# PROIECT_TSC.net
KiCad netlist of a schematic drawn in EAGLE
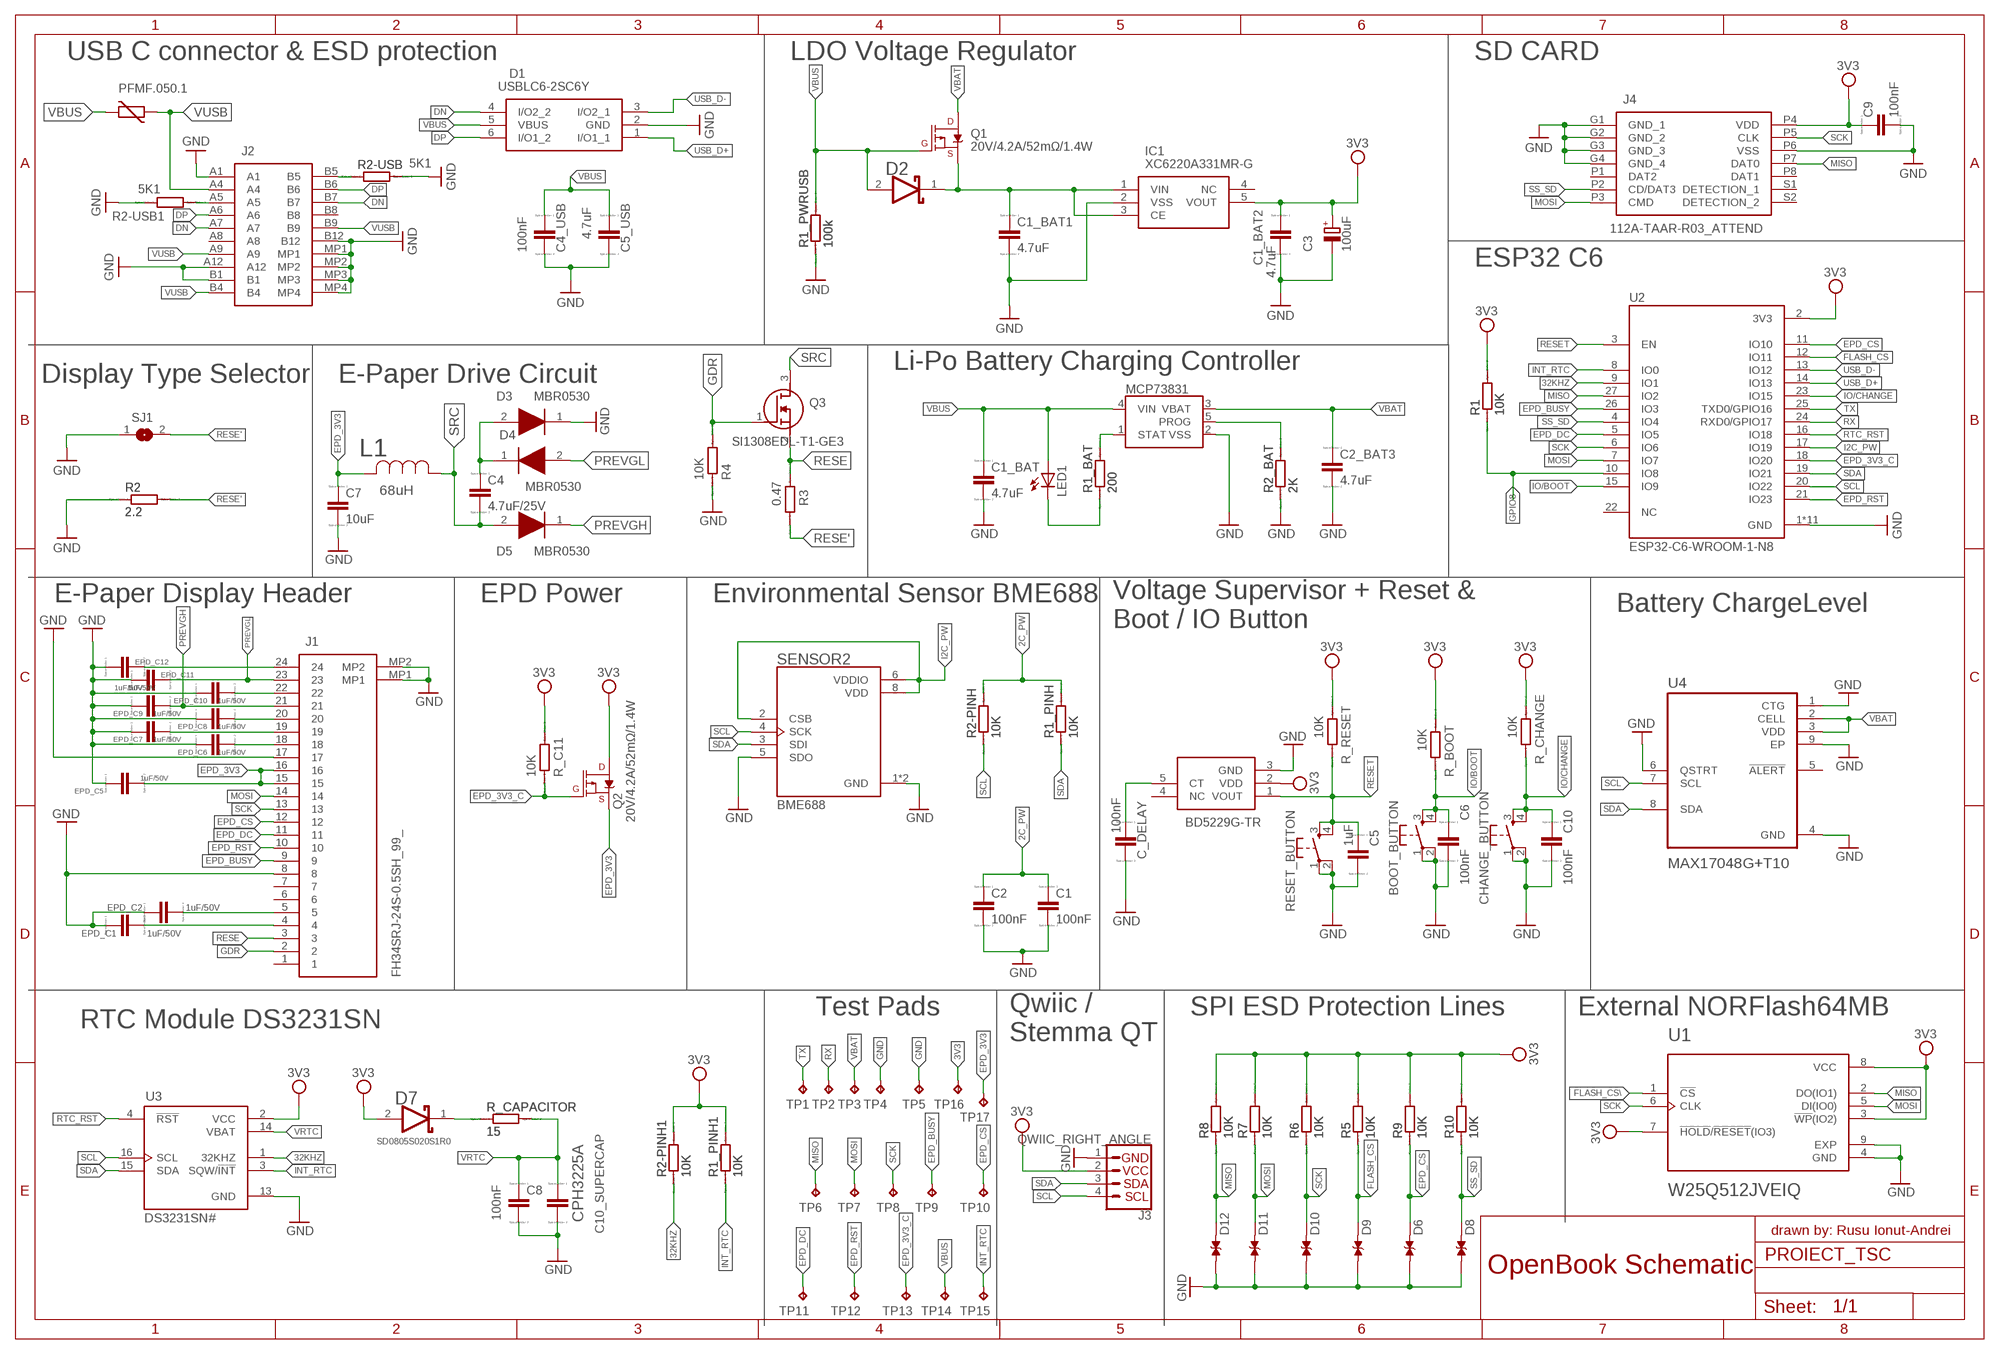
[diagram p0: schematic, sheet 1]

(export (version "E")
  (design (tool "Eeschema 10.0.6"))
  (components
    (comp (ref "BOOT_BUTTON")
      (value "BUTTON_CUSYOMV1")
      (footprint "eagle-import:MYBUTTON")
      (libsource (lib "eagle-import") (part "BUTTON_CUSYOMV1"))
    )
    (comp (ref "C1")
      (value "100nF")
      (footprint "eagle-import:ESP32_WROVER_EAGLE-LTSPICE_C0402")
      (libsource (lib "eagle-import") (part "ESP32_WROVER_EAGLE-LTSPICE_CC0402"))
    )
    (comp (ref "C1_BAT")
      (value "4.7uF")
      (footprint "eagle-import:ESP32_WROVER_EAGLE-LTSPICE_C0402")
      (libsource (lib "eagle-import") (part "ESP32_WROVER_EAGLE-LTSPICE_CC0402"))
    )
    (comp (ref "C1_BAT1")
      (value "4.7uF")
      (footprint "eagle-import:ESP32_WROVER_EAGLE-LTSPICE_C0402")
      (libsource (lib "eagle-import") (part "ESP32_WROVER_EAGLE-LTSPICE_CC0402"))
    )
    (comp (ref "C1_BAT2")
      (value "4.7uF")
      (footprint "eagle-import:EAGLE-LTSPICE_C0402")
      (libsource (lib "eagle-import") (part "EAGLE-LTSPICE_CC0402"))
    )
    (comp (ref "C2")
      (value "100nF")
      (footprint "eagle-import:ESP32_WROVER_EAGLE-LTSPICE_C0402")
      (libsource (lib "eagle-import") (part "ESP32_WROVER_EAGLE-LTSPICE_CC0402"))
    )
    (comp (ref "C2_BAT3")
      (value "4.7uF")
      (footprint "eagle-import:ESP32_WROVER_EAGLE-LTSPICE_C0402")
      (libsource (lib "eagle-import") (part "ESP32_WROVER_EAGLE-LTSPICE_CC0402"))
    )
    (comp (ref "C3")
      (value "100uF")
      (footprint "eagle-import:RCL_CT3528")
      (libsource (lib "eagle-import") (part "RCL_CPOL-EUCT3528"))
    )
    (comp (ref "C4")
      (value "4.7uF/25V")
      (footprint "eagle-import:ESP32_WROVER_EAGLE-LTSPICE_C0402")
      (libsource (lib "eagle-import") (part "ESP32_WROVER_EAGLE-LTSPICE_CC0402"))
    )
    (comp (ref "C4_USB")
      (value "100nF")
      (footprint "eagle-import:EAGLE-LTSPICE_C0402")
      (libsource (lib "eagle-import") (part "EAGLE-LTSPICE_CC0402"))
    )
    (comp (ref "C5")
      (value "1uF")
      (footprint "eagle-import:ESP32_WROVER_EAGLE-LTSPICE_C0402")
      (libsource (lib "eagle-import") (part "ESP32_WROVER_EAGLE-LTSPICE_CC0402"))
    )
    (comp (ref "C5_USB")
      (value "4.7uF")
      (footprint "eagle-import:EAGLE-LTSPICE_C0402")
      (libsource (lib "eagle-import") (part "EAGLE-LTSPICE_CC0402"))
    )
    (comp (ref "C6")
      (value "100nF")
      (footprint "eagle-import:ESP32_WROVER_EAGLE-LTSPICE_C0402")
      (libsource (lib "eagle-import") (part "ESP32_WROVER_EAGLE-LTSPICE_CC0402"))
    )
    (comp (ref "C7")
      (value "10uF")
      (footprint "eagle-import:EAGLE-LTSPICE_C0402")
      (libsource (lib "eagle-import") (part "EAGLE-LTSPICE_CC0402"))
    )
    (comp (ref "C8")
      (value "100nF")
      (footprint "eagle-import:ESP32_WROVER_EAGLE-LTSPICE_C0402")
      (libsource (lib "eagle-import") (part "ESP32_WROVER_EAGLE-LTSPICE_CC0402"))
    )
    (comp (ref "C9")
      (value "100nF")
      (footprint "eagle-import:ESP32_WROVER_EAGLE-LTSPICE_C0402")
      (libsource (lib "eagle-import") (part "ESP32_WROVER_EAGLE-LTSPICE_CC0402"))
    )
    (comp (ref "C10")
      (value "100nF")
      (footprint "eagle-import:ESP32_WROVER_EAGLE-LTSPICE_C0402")
      (libsource (lib "eagle-import") (part "ESP32_WROVER_EAGLE-LTSPICE_CC0402"))
    )
    (comp (ref "C10_SUPERCAP")
      (value "ESP32_WROVER_EAGLE-LTSPICE_CC0402")
      (footprint "eagle-import:ESP32_WROVER_EAGLE-LTSPICE_C0402")
      (libsource (lib "eagle-import") (part "ESP32_WROVER_EAGLE-LTSPICE_CC0402"))
    )
    (comp (ref "CHANGE_BUTTON")
      (value "BUTTON_CUSYOMV1")
      (footprint "eagle-import:MYBUTTON")
      (libsource (lib "eagle-import") (part "BUTTON_CUSYOMV1"))
    )
    (comp (ref "C_DELAY")
      (value "100nF")
      (footprint "eagle-import:ESP32_WROVER_EAGLE-LTSPICE_C0402")
      (libsource (lib "eagle-import") (part "ESP32_WROVER_EAGLE-LTSPICE_CC0402"))
    )
    (comp (ref "D1")
      (value "USBLC6-2SC6Y")
      (footprint "eagle-import:SOT95P280X145-6N")
      (fields (field (name "MF") "STMicroelectronics"))
      (libsource (lib "eagle-import") (part "USBLC6-2SC6Y"))
    )
    (comp (ref "D2")
      (value "ESP32_WROVER_AVX---SD0805S020S1R0_AVX_SD0805S020S1R0_0_0AVX_SD0805S020S1R0_0_0")
      (footprint "eagle-import:ESP32_WROVER_AVX---SD0805S020S1R0_AVX_SD0805S020S1R0_0")
      (fields
        (field (name "DIGIKEY_PART_NUMBER") "478-7800-1-ND")
        (field (name "MF") "AVX")
        (field (name "MOUSER_PART_NUMBER") "581-SD0805S020S1R0")
      )
      (libsource (lib "eagle-import") (part "ESP32_WROVER_AVX---SD0805S020S1R0_AVX_SD0805S020S1R0_0_0AVX_SD0805S020S1R0_0_0"))
    )
    (comp (ref "D3")
      (value "MBR0530")
      (footprint "eagle-import:SOD3716X135N")
      (fields (field (name "MF") "ON Semiconductor"))
      (libsource (lib "eagle-import") (part "MBR0530"))
    )
    (comp (ref "D4")
      (value "MBR0530")
      (footprint "eagle-import:SOD3716X135N")
      (fields (field (name "MF") "ON Semiconductor"))
      (libsource (lib "eagle-import") (part "MBR0530"))
    )
    (comp (ref "D5")
      (value "MBR0530")
      (footprint "eagle-import:SOD3716X135N")
      (fields (field (name "MF") "ON Semiconductor"))
      (libsource (lib "eagle-import") (part "MBR0530"))
    )
    (comp (ref "D6")
      (value "PGB1010603MR")
      (footprint "eagle-import:DIOC1608X36N")
      (fields (field (name "MF") "Littelfuse Inc."))
      (libsource (lib "eagle-import") (part "PGB1010603MR"))
    )
    (comp (ref "D7")
      (value "ESP32_WROVER_AVX---SD0805S020S1R0_AVX_SD0805S020S1R0_0_0AVX_SD0805S020S1R0_0_0")
      (footprint "eagle-import:ESP32_WROVER_AVX---SD0805S020S1R0_AVX_SD0805S020S1R0_0")
      (fields
        (field (name "DIGIKEY_PART_NUMBER") "478-7800-1-ND")
        (field (name "MF") "AVX")
        (field (name "MOUSER_PART_NUMBER") "581-SD0805S020S1R0")
      )
      (libsource (lib "eagle-import") (part "ESP32_WROVER_AVX---SD0805S020S1R0_AVX_SD0805S020S1R0_0_0AVX_SD0805S020S1R0_0_0"))
    )
    (comp (ref "D8")
      (value "PGB1010603MR")
      (footprint "eagle-import:DIOC1608X36N")
      (fields (field (name "MF") "Littelfuse Inc."))
      (libsource (lib "eagle-import") (part "PGB1010603MR"))
    )
    (comp (ref "D9")
      (value "PGB1010603MR")
      (footprint "eagle-import:DIOC1608X36N")
      (fields (field (name "MF") "Littelfuse Inc."))
      (libsource (lib "eagle-import") (part "PGB1010603MR"))
    )
    (comp (ref "D10")
      (value "PGB1010603MR")
      (footprint "eagle-import:DIOC1608X36N")
      (fields (field (name "MF") "Littelfuse Inc."))
      (libsource (lib "eagle-import") (part "PGB1010603MR"))
    )
    (comp (ref "D11")
      (value "PGB1010603MR")
      (footprint "eagle-import:DIOC1608X36N")
      (fields (field (name "MF") "Littelfuse Inc."))
      (libsource (lib "eagle-import") (part "PGB1010603MR"))
    )
    (comp (ref "D12")
      (value "PGB1010603MR")
      (footprint "eagle-import:DIOC1608X36N")
      (fields (field (name "MF") "Littelfuse Inc."))
      (libsource (lib "eagle-import") (part "PGB1010603MR"))
    )
    (comp (ref "EPD_C1")
      (value "1uF/50V")
      (footprint "eagle-import:ESP32_WROVER_EAGLE-LTSPICE_C0402")
      (libsource (lib "eagle-import") (part "ESP32_WROVER_EAGLE-LTSPICE_CC0402"))
    )
    (comp (ref "EPD_C2")
      (value "1uF/50V")
      (footprint "eagle-import:ESP32_WROVER_EAGLE-LTSPICE_C0402")
      (libsource (lib "eagle-import") (part "ESP32_WROVER_EAGLE-LTSPICE_CC0402"))
    )
    (comp (ref "EPD_C5")
      (value "1uF/50V")
      (footprint "eagle-import:ESP32_WROVER_EAGLE-LTSPICE_C0402")
      (libsource (lib "eagle-import") (part "ESP32_WROVER_EAGLE-LTSPICE_CC0402"))
    )
    (comp (ref "EPD_C6")
      (value "1uF/50V")
      (footprint "eagle-import:ESP32_WROVER_EAGLE-LTSPICE_C0402")
      (libsource (lib "eagle-import") (part "ESP32_WROVER_EAGLE-LTSPICE_CC0402"))
    )
    (comp (ref "EPD_C7")
      (value "1uF/50V")
      (footprint "eagle-import:ESP32_WROVER_EAGLE-LTSPICE_C0402")
      (libsource (lib "eagle-import") (part "ESP32_WROVER_EAGLE-LTSPICE_CC0402"))
    )
    (comp (ref "EPD_C8")
      (value "1uF/50V")
      (footprint "eagle-import:ESP32_WROVER_EAGLE-LTSPICE_C0402")
      (libsource (lib "eagle-import") (part "ESP32_WROVER_EAGLE-LTSPICE_CC0402"))
    )
    (comp (ref "EPD_C9")
      (value "1uF/50V")
      (footprint "eagle-import:ESP32_WROVER_EAGLE-LTSPICE_C0402")
      (libsource (lib "eagle-import") (part "ESP32_WROVER_EAGLE-LTSPICE_CC0402"))
    )
    (comp (ref "EPD_C10")
      (value "1uF/50V")
      (footprint "eagle-import:ESP32_WROVER_EAGLE-LTSPICE_C0402")
      (libsource (lib "eagle-import") (part "ESP32_WROVER_EAGLE-LTSPICE_CC0402"))
    )
    (comp (ref "EPD_C11")
      (value "1uF/50V")
      (footprint "eagle-import:ESP32_WROVER_EAGLE-LTSPICE_C0402")
      (libsource (lib "eagle-import") (part "ESP32_WROVER_EAGLE-LTSPICE_CC0402"))
    )
    (comp (ref "EPD_C12")
      (value "1uF/50V")
      (footprint "eagle-import:ESP32_WROVER_EAGLE-LTSPICE_C0402")
      (libsource (lib "eagle-import") (part "ESP32_WROVER_EAGLE-LTSPICE_CC0402"))
    )
    (comp (ref "IC1")
      (value "XC6220A331MR-G")
      (footprint "eagle-import:SOT95P280X120-5N")
      (fields (field (name "MOUSER_PART_NUMBER") "865-XC6220A331MR-G"))
      (libsource (lib "eagle-import") (part "XC6220A331MR-G"))
    )
    (comp (ref "IC2")
      (value "BD5229G-TR")
      (footprint "eagle-import:SOT95P280X125-5N")
      (fields (field (name "MOUSER_PART_NUMBER") "755-BD5229G-TR"))
      (libsource (lib "eagle-import") (part "BD5229G-TR"))
    )
    (comp (ref "J1")
      (value "FH34SRJ-24S-0.5SH_99_")
      (footprint "eagle-import:FH34SRJ24S05SH99")
      (fields
        (field (name "MANUFACTURER_PART_NUMBER") "FH34SRJ-24S-0.5SH(99)")
        (field (name "MOUSER_PART_NUMBER") "798-FH34SRJ24S05SH99")
      )
      (libsource (lib "eagle-import") (part "FH34SRJ-24S-0.5SH_99_"))
    )
    (comp (ref "J2")
      (value "SAMACSYS_PARTS_USB4110-GF-A")
      (footprint "eagle-import:SAMACSYS_PARTS_USB4110GFA")
      (fields
        (field (name "MANUFACTURER_PART_NUMBER") "USB4110-GF-A")
        (field (name "MOUSER_PART_NUMBER") "640-USB4110-GF-A")
      )
      (libsource (lib "eagle-import") (part "SAMACSYS_PARTS_USB4110-GF-A"))
    )
    (comp (ref "J3")
      (value "QWIIC_RIGHT_ANGLE")
      (footprint "eagle-import:JST04_1MM_RA")
      (libsource (lib "eagle-import") (part "QWIIC_CONNECTORJS-1MM"))
    )
    (comp (ref "J4")
      (value "112A-TAAR-R03_ATTEND")
      (footprint "eagle-import:112ATAARR03ATTEND")
      (fields (field (name "MANUFACTURER_PART_NUMBER") "112A-TAAR-R03 ATTEND"))
      (libsource (lib "eagle-import") (part "112A-TAAR-R03_ATTEND"))
    )
    (comp (ref "L1")
      (value "68uH")
      (footprint "eagle-import:IND_4828-WE-TPC_WRE")
      (fields
        (field (name "MANUFACTURER_PART_NUMBER") "744043680")
        (field (name "COPYRIGHT") "Copyright (C) 2024 Ultra Librarian. All rights reserved.")
      )
      (libsource (lib "eagle-import") (part "744043680IND_4828-WE-TPC_WRE"))
    )
    (comp (ref "LED1")
      (value "ADAFRUIT_LEDCHIP-LED0603")
      (footprint "eagle-import:ADAFRUIT_CHIP-LED0603")
      (libsource (lib "eagle-import") (part "ADAFRUIT_LEDCHIP-LED0603"))
    )
    (comp (ref "MCP73831")
      (value "ESP32_WROVER_SPARKFUN-IC-POWER_MCP73831")
      (footprint "eagle-import:ESP32_WROVER_SPARKFUN-IC-POWER_SOT23-5")
      (libsource (lib "eagle-import") (part "ESP32_WROVER_SPARKFUN-IC-POWER_MCP73831"))
    )
    (comp (ref "PFMF.050.1")
      (value "ESP32C6_VARISTORCN1812")
      (footprint "eagle-import:ESP32C6_VARISTOR_CT_CN1812")
      (libsource (lib "eagle-import") (part "ESP32C6_VARISTORCN1812"))
    )
    (comp (ref "Q1")
      (value "20V/4.2A/52mΩ/1.4W")
      (footprint "eagle-import:ESP32_WROVER_SPARKFUN-DISCRETESEMI_SOT23-3")
      (libsource (lib "eagle-import") (part "ESP32_WROVER_SPARKFUN-DISCRETESEMI_MOSFET_PCH-DMG2305UX-7"))
    )
    (comp (ref "Q2")
      (value "20V/4.2A/52mΩ/1.4W")
      (footprint "eagle-import:ESP32_WROVER_SPARKFUN-DISCRETESEMI_SOT23-3")
      (libsource (lib "eagle-import") (part "ESP32_WROVER_SPARKFUN-DISCRETESEMI_MOSFET_PCH-DMG2305UX-7"))
    )
    (comp (ref "Q3")
      (value "SI1308EDL-T1-GE3")
      (footprint "eagle-import:SOT65P210X110-3N")
      (fields (field (name "MF") "Vishay Siliconix"))
      (libsource (lib "eagle-import") (part "SI1308EDL-T1-GE3"))
    )
    (comp (ref "R1")
      (value "10K")
      (footprint "eagle-import:ESP32_WROVER_EAGLE-LTSPICE_R0402")
      (libsource (lib "eagle-import") (part "ESP32_WROVER_EAGLE-LTSPICE_RR0402"))
    )
    (comp (ref "R1_BAT")
      (value "200")
      (footprint "eagle-import:ESP32_WROVER_EAGLE-LTSPICE_R0402")
      (libsource (lib "eagle-import") (part "ESP32_WROVER_EAGLE-LTSPICE_RR0402"))
    )
    (comp (ref "R1_PINH")
      (value "10K")
      (footprint "eagle-import:ESP32_WROVER_EAGLE-LTSPICE_R0402")
      (libsource (lib "eagle-import") (part "ESP32_WROVER_EAGLE-LTSPICE_RR0402"))
    )
    (comp (ref "R1_PINH1")
      (value "10K")
      (footprint "eagle-import:ESP32_WROVER_EAGLE-LTSPICE_R0402")
      (libsource (lib "eagle-import") (part "ESP32_WROVER_EAGLE-LTSPICE_RR0402"))
    )
    (comp (ref "R1_PWRUSB")
      (value "100k")
      (footprint "eagle-import:ESP32_WROVER_EAGLE-LTSPICE_R0402")
      (libsource (lib "eagle-import") (part "ESP32_WROVER_EAGLE-LTSPICE_RR0402"))
    )
    (comp (ref "R2")
      (value "2.2")
      (footprint "eagle-import:ESP32_WROVER_EAGLE-LTSPICE_R0402")
      (libsource (lib "eagle-import") (part "ESP32_WROVER_EAGLE-LTSPICE_RR0402"))
    )
    (comp (ref "R2-PINH")
      (value "10K")
      (footprint "eagle-import:ESP32_WROVER_EAGLE-LTSPICE_R0402")
      (libsource (lib "eagle-import") (part "ESP32_WROVER_EAGLE-LTSPICE_RR0402"))
    )
    (comp (ref "R2-PINH1")
      (value "10K")
      (footprint "eagle-import:ESP32_WROVER_EAGLE-LTSPICE_R0402")
      (libsource (lib "eagle-import") (part "ESP32_WROVER_EAGLE-LTSPICE_RR0402"))
    )
    (comp (ref "R2-USB")
      (value "5K1")
      (footprint "eagle-import:ESP32_WROVER_EAGLE-LTSPICE_R0402")
      (libsource (lib "eagle-import") (part "ESP32_WROVER_EAGLE-LTSPICE_RR0402"))
    )
    (comp (ref "R2-USB1")
      (value "5K1")
      (footprint "eagle-import:ESP32_WROVER_EAGLE-LTSPICE_R0402")
      (libsource (lib "eagle-import") (part "ESP32_WROVER_EAGLE-LTSPICE_RR0402"))
    )
    (comp (ref "R2_BAT")
      (value "2K")
      (footprint "eagle-import:ESP32_WROVER_EAGLE-LTSPICE_R0402")
      (libsource (lib "eagle-import") (part "ESP32_WROVER_EAGLE-LTSPICE_RR0402"))
    )
    (comp (ref "R3")
      (value "0.47")
      (footprint "eagle-import:ESP32_WROVER_EAGLE-LTSPICE_R0402")
      (libsource (lib "eagle-import") (part "ESP32_WROVER_EAGLE-LTSPICE_RR0402"))
    )
    (comp (ref "R4")
      (value "10K")
      (footprint "eagle-import:ESP32_WROVER_EAGLE-LTSPICE_R0402")
      (libsource (lib "eagle-import") (part "ESP32_WROVER_EAGLE-LTSPICE_RR0402"))
    )
    (comp (ref "R5")
      (value "10K")
      (footprint "eagle-import:ESP32_WROVER_EAGLE-LTSPICE_R0402")
      (libsource (lib "eagle-import") (part "ESP32_WROVER_EAGLE-LTSPICE_RR0402"))
    )
    (comp (ref "R6")
      (value "10K")
      (footprint "eagle-import:ESP32_WROVER_EAGLE-LTSPICE_R0402")
      (libsource (lib "eagle-import") (part "ESP32_WROVER_EAGLE-LTSPICE_RR0402"))
    )
    (comp (ref "R7")
      (value "10K")
      (footprint "eagle-import:ESP32_WROVER_EAGLE-LTSPICE_R0402")
      (libsource (lib "eagle-import") (part "ESP32_WROVER_EAGLE-LTSPICE_RR0402"))
    )
    (comp (ref "R8")
      (value "10K")
      (footprint "eagle-import:ESP32_WROVER_EAGLE-LTSPICE_R0402")
      (libsource (lib "eagle-import") (part "ESP32_WROVER_EAGLE-LTSPICE_RR0402"))
    )
    (comp (ref "R9")
      (value "10K")
      (footprint "eagle-import:ESP32_WROVER_EAGLE-LTSPICE_R0402")
      (libsource (lib "eagle-import") (part "ESP32_WROVER_EAGLE-LTSPICE_RR0402"))
    )
    (comp (ref "R10")
      (value "10K")
      (footprint "eagle-import:ESP32_WROVER_EAGLE-LTSPICE_R0402")
      (libsource (lib "eagle-import") (part "ESP32_WROVER_EAGLE-LTSPICE_RR0402"))
    )
    (comp (ref "RESET_BUTTON")
      (value "BUTTON_CUSYOMV1")
      (footprint "eagle-import:MYBUTTON")
      (libsource (lib "eagle-import") (part "BUTTON_CUSYOMV1"))
    )
    (comp (ref "R_BOOT")
      (value "10K")
      (footprint "eagle-import:ESP32_WROVER_EAGLE-LTSPICE_R0402")
      (libsource (lib "eagle-import") (part "ESP32_WROVER_EAGLE-LTSPICE_RR0402"))
    )
    (comp (ref "R_C11")
      (value "10K")
      (footprint "eagle-import:ESP32_WROVER_EAGLE-LTSPICE_R0402")
      (libsource (lib "eagle-import") (part "ESP32_WROVER_EAGLE-LTSPICE_RR0402"))
    )
    (comp (ref "R_CAPACITOR")
      (value "15")
      (footprint "eagle-import:ESP32_WROVER_EAGLE-LTSPICE_R0402")
      (libsource (lib "eagle-import") (part "ESP32_WROVER_EAGLE-LTSPICE_RR0402"))
    )
    (comp (ref "R_CHANGE")
      (value "10K")
      (footprint "eagle-import:ESP32_WROVER_EAGLE-LTSPICE_R0402")
      (libsource (lib "eagle-import") (part "ESP32_WROVER_EAGLE-LTSPICE_RR0402"))
    )
    (comp (ref "R_RESET")
      (value "10K")
      (footprint "eagle-import:ESP32_WROVER_EAGLE-LTSPICE_R0402")
      (libsource (lib "eagle-import") (part "ESP32_WROVER_EAGLE-LTSPICE_RR0402"))
    )
    (comp (ref "SENSOR2")
      (value "ESP32_WROVER_BME680_BME680")
      (footprint "eagle-import:ESP32_WROVER_BME680_PSON80P300X300X100-8N")
      (fields (field (name "MF") "Bosch Sensortec") (field (name "MP") "BME680"))
      (libsource (lib "eagle-import") (part "ESP32_WROVER_BME680_BME680"))
    )
    (comp (ref "SJ1") (value "SJ") (footprint "eagle-import:SJ") (libsource (lib "eagle-import") (part "SJ")))
    (comp (ref "TP1")
      (value "TPTP20R")
      (footprint "eagle-import:TP20R")
      (libsource (lib "eagle-import") (part "TPTP20R"))
    )
    (comp (ref "TP2")
      (value "TPTP20R")
      (footprint "eagle-import:TP20R")
      (libsource (lib "eagle-import") (part "TPTP20R"))
    )
    (comp (ref "TP3")
      (value "TPTP20R")
      (footprint "eagle-import:TP20R")
      (libsource (lib "eagle-import") (part "TPTP20R"))
    )
    (comp (ref "TP4")
      (value "TPTP20R")
      (footprint "eagle-import:TP20R")
      (libsource (lib "eagle-import") (part "TPTP20R"))
    )
    (comp (ref "TP5")
      (value "TPTP20R")
      (footprint "eagle-import:TP20R")
      (libsource (lib "eagle-import") (part "TPTP20R"))
    )
    (comp (ref "TP6")
      (value "TPTP20R")
      (footprint "eagle-import:TP20R")
      (libsource (lib "eagle-import") (part "TPTP20R"))
    )
    (comp (ref "TP7")
      (value "TPTP20R")
      (footprint "eagle-import:TP20R")
      (libsource (lib "eagle-import") (part "TPTP20R"))
    )
    (comp (ref "TP8")
      (value "TPTP20R")
      (footprint "eagle-import:TP20R")
      (libsource (lib "eagle-import") (part "TPTP20R"))
    )
    (comp (ref "TP9")
      (value "TPTP20R")
      (footprint "eagle-import:TP20R")
      (libsource (lib "eagle-import") (part "TPTP20R"))
    )
    (comp (ref "TP10")
      (value "TPTP20R")
      (footprint "eagle-import:TP20R")
      (libsource (lib "eagle-import") (part "TPTP20R"))
    )
    (comp (ref "TP11")
      (value "TPTP20R")
      (footprint "eagle-import:TP20R")
      (libsource (lib "eagle-import") (part "TPTP20R"))
    )
    (comp (ref "TP12")
      (value "TPTP20R")
      (footprint "eagle-import:TP20R")
      (libsource (lib "eagle-import") (part "TPTP20R"))
    )
    (comp (ref "TP13")
      (value "TPTP20R")
      (footprint "eagle-import:TP20R")
      (libsource (lib "eagle-import") (part "TPTP20R"))
    )
    (comp (ref "TP14")
      (value "TPTP20R")
      (footprint "eagle-import:TP20R")
      (libsource (lib "eagle-import") (part "TPTP20R"))
    )
    (comp (ref "TP15")
      (value "TPTP20R")
      (footprint "eagle-import:TP20R")
      (libsource (lib "eagle-import") (part "TPTP20R"))
    )
    (comp (ref "TP16")
      (value "TPTP20R")
      (footprint "eagle-import:TP20R")
      (libsource (lib "eagle-import") (part "TPTP20R"))
    )
    (comp (ref "TP17")
      (value "TPTP20R")
      (footprint "eagle-import:TP20R")
      (libsource (lib "eagle-import") (part "TPTP20R"))
    )
    (comp (ref "U1")
      (value "W25Q512JVEIQ")
      (footprint "eagle-import:SON127P600X800X80-9N")
      (fields (field (name "MF") "Winbond Electronics"))
      (libsource (lib "eagle-import") (part "W25Q512JVEIQ"))
    )
    (comp (ref "U2")
      (value "ESP32-C6-WROOM-1-N8")
      (footprint "eagle-import:XCVR_ESP32-C6-WROOM-1-N8")
      (fields (field (name "MF") "Espressif Systems"))
      (libsource (lib "eagle-import") (part "ESP32-C6-WROOM-1-N8"))
    )
    (comp (ref "U3")
      (value "DS3231SN#")
      (footprint "eagle-import:SOIC127P1032X265-16N")
      (fields (field (name "MF") "Analog Devices"))
      (libsource (lib "eagle-import") (part "DS3231SN#"))
    )
    (comp (ref "U4")
      (value "MAX17048G+T10")
      (footprint "eagle-import:SON50P200X200X80-9N")
      (fields (field (name "MF") "Analog Devices"))
      (libsource (lib "eagle-import") (part "MAX17048G+T10"))
    )
  )
  (nets
    (net (code "1") (name "2C_PW") (class "Default")
      (node (ref "C1") (pin "1") (pinfunction "1_1") (pintype "passive"))
      (node (ref "C2") (pin "1") (pinfunction "1_1") (pintype "passive"))
      (node (ref "R1_PINH") (pin "2") (pinfunction "2_2") (pintype "passive"))
      (node (ref "R2-PINH") (pin "2") (pinfunction "2_2") (pintype "passive"))
    )
    (net (code "2") (name "3V3") (class "Default")
      (node (ref "C1_BAT2") (pin "1") (pinfunction "1_1") (pintype "passive"))
      (node (ref "C3") (pin "+") (pinfunction "+_+") (pintype "passive"))
      (node (ref "C9") (pin "1") (pinfunction "1_1") (pintype "passive"))
      (node (ref "D7") (pin "2") (pinfunction "ANODE_2") (pintype "bidirectional"))
      (node (ref "IC1") (pin "5") (pinfunction "VOUT_5") (pintype "bidirectional"))
      (node (ref "IC2") (pin "2") (pinfunction "VDD_2") (pintype "bidirectional"))
      (node (ref "J3") (pin "2") (pinfunction "2_2") (pintype "power_in"))
      (node (ref "J4") (pin "P4") (pinfunction "VDD_P4") (pintype "bidirectional"))
      (node (ref "Q2") (pin "3") (pinfunction "D_3") (pintype "bidirectional"))
      (node (ref "R1") (pin "2") (pinfunction "2_2") (pintype "passive"))
      (node (ref "R10") (pin "2") (pinfunction "2_2") (pintype "passive"))
      (node (ref "R1_PINH1") (pin "2") (pinfunction "2_2") (pintype "passive"))
      (node (ref "R2-PINH1") (pin "2") (pinfunction "2_2") (pintype "passive"))
      (node (ref "R5") (pin "2") (pinfunction "2_2") (pintype "passive"))
      (node (ref "R6") (pin "2") (pinfunction "2_2") (pintype "passive"))
      (node (ref "R7") (pin "2") (pinfunction "2_2") (pintype "passive"))
      (node (ref "R8") (pin "2") (pinfunction "2_2") (pintype "passive"))
      (node (ref "R9") (pin "2") (pinfunction "2_2") (pintype "passive"))
      (node (ref "R_BOOT") (pin "2") (pinfunction "2_2") (pintype "passive"))
      (node (ref "R_C11") (pin "2") (pinfunction "2_2") (pintype "passive"))
      (node (ref "R_CHANGE") (pin "2") (pinfunction "2_2") (pintype "passive"))
      (node (ref "R_RESET") (pin "2") (pinfunction "2_2") (pintype "passive"))
      (node (ref "TP16") (pin "TP") (pinfunction "TP_TP") (pintype "input"))
      (node (ref "U1") (pin "3") (pinfunction "~{WP}(IO2)_3") (pintype "bidirectional"))
      (node (ref "U1") (pin "7") (pinfunction "~{HOLD}/~{RESET}(IO3)_7") (pintype "bidirectional"))
      (node (ref "U1") (pin "8") (pinfunction "VCC_8") (pintype "power_in"))
      (node (ref "U2") (pin "2") (pinfunction "3V3_2") (pintype "power_in"))
      (node (ref "U3") (pin "2") (pinfunction "VCC_2") (pintype "power_in"))
    )
    (net (code "3") (name "32KHZ") (class "Default")
      (node (ref "R2-PINH1") (pin "1") (pinfunction "1_1") (pintype "passive"))
      (node (ref "U2") (pin "9") (pinfunction "IO1_9") (pintype "bidirectional"))
      (node (ref "U3") (pin "1") (pinfunction "32KHZ_1") (pintype "output"))
    )
    (net (code "4") (name "DN") (class "Default")
      (node (ref "D1") (pin "4") (pinfunction "I/O2_2_4") (pintype "bidirectional"))
      (node (ref "J2") (pin "A7") (pinfunction "A7_A7") (pintype "bidirectional"))
      (node (ref "J2") (pin "B7") (pinfunction "B7_B7") (pintype "bidirectional"))
    )
    (net (code "5") (name "DP") (class "Default")
      (node (ref "D1") (pin "6") (pinfunction "I/O1_2_6") (pintype "bidirectional"))
      (node (ref "J2") (pin "A6") (pinfunction "A6_A6") (pintype "bidirectional"))
      (node (ref "J2") (pin "B6") (pinfunction "B6_B6") (pintype "bidirectional"))
    )
    (net (code "6") (name "EPD_3V3") (class "Default")
      (node (ref "C7") (pin "1") (pinfunction "1_1") (pintype "passive"))
      (node (ref "EPD_C5") (pin "2") (pinfunction "2_2") (pintype "passive"))
      (node (ref "J1") (pin "15") (pinfunction "15_15") (pintype "bidirectional"))
      (node (ref "J1") (pin "16") (pinfunction "16_16") (pintype "bidirectional"))
      (node (ref "L1") (pin "2") (pinfunction "2_2") (pintype "passive"))
      (node (ref "Q2") (pin "2") (pinfunction "S_2") (pintype "bidirectional"))
      (node (ref "TP17") (pin "TP") (pinfunction "TP_TP") (pintype "input"))
    )
    (net (code "7") (name "EPD_3V3_C") (class "Default")
      (node (ref "Q2") (pin "1") (pinfunction "G_1") (pintype "bidirectional"))
      (node (ref "R_C11") (pin "1") (pinfunction "1_1") (pintype "passive"))
      (node (ref "TP13") (pin "TP") (pinfunction "TP_TP") (pintype "input"))
      (node (ref "U2") (pin "18") (pinfunction "IO20_18") (pintype "bidirectional"))
    )
    (net (code "8") (name "EPD_BUSY") (class "Default")
      (node (ref "J1") (pin "9") (pinfunction "9_9") (pintype "bidirectional"))
      (node (ref "TP9") (pin "TP") (pinfunction "TP_TP") (pintype "input"))
      (node (ref "U2") (pin "26") (pinfunction "IO3_26") (pintype "bidirectional"))
    )
    (net (code "9") (name "EPD_CS") (class "Default")
      (node (ref "D6") (pin "2") (pinfunction "2_2") (pintype "passive"))
      (node (ref "J1") (pin "12") (pinfunction "12_12") (pintype "bidirectional"))
      (node (ref "R9") (pin "1") (pinfunction "1_1") (pintype "passive"))
      (node (ref "TP10") (pin "TP") (pinfunction "TP_TP") (pintype "input"))
      (node (ref "U2") (pin "11") (pinfunction "IO10_11") (pintype "bidirectional"))
    )
    (net (code "10") (name "EPD_DC") (class "Default")
      (node (ref "J1") (pin "11") (pinfunction "11_11") (pintype "bidirectional"))
      (node (ref "TP11") (pin "TP") (pinfunction "TP_TP") (pintype "input"))
      (node (ref "U2") (pin "5") (pinfunction "IO5_5") (pintype "bidirectional"))
    )
    (net (code "11") (name "EPD_RST") (class "Default")
      (node (ref "J1") (pin "10") (pinfunction "10_10") (pintype "bidirectional"))
      (node (ref "TP12") (pin "TP") (pinfunction "TP_TP") (pintype "input"))
      (node (ref "U2") (pin "21") (pinfunction "IO23_21") (pintype "bidirectional"))
    )
    (net (code "12") (name "FLASH_CS") (class "Default")
      (node (ref "D9") (pin "2") (pinfunction "2_2") (pintype "passive"))
      (node (ref "R5") (pin "1") (pinfunction "1_1") (pintype "passive"))
      (node (ref "U2") (pin "12") (pinfunction "IO11_12") (pintype "bidirectional"))
    )
    (net (code "13") (name "FLASH_CS\\") (class "Default")
      (node (ref "U1") (pin "1") (pinfunction "~{CS}_1") (pintype "input"))
    )
    (net (code "14") (name "GDR") (class "Default")
      (node (ref "J1") (pin "2") (pinfunction "2_2") (pintype "bidirectional"))
      (node (ref "Q3") (pin "1") (pinfunction "G_1") (pintype "bidirectional"))
      (node (ref "R4") (pin "2") (pinfunction "2_2") (pintype "passive"))
    )
    (net (code "15") (name "GND") (class "Default")
      (node (ref "BOOT_BUTTON") (pin "1") (pinfunction "1_1") (pintype "passive"))
      (node (ref "BOOT_BUTTON") (pin "2") (pinfunction "2_2") (pintype "passive"))
      (node (ref "C1") (pin "2") (pinfunction "2_2") (pintype "passive"))
      (node (ref "C10") (pin "2") (pinfunction "2_2") (pintype "passive"))
      (node (ref "C10_SUPERCAP") (pin "2") (pinfunction "2_2") (pintype "passive"))
      (node (ref "C1_BAT") (pin "2") (pinfunction "2_2") (pintype "passive"))
      (node (ref "C1_BAT1") (pin "2") (pinfunction "2_2") (pintype "passive"))
      (node (ref "C1_BAT2") (pin "2") (pinfunction "2_2") (pintype "passive"))
      (node (ref "C2") (pin "2") (pinfunction "2_2") (pintype "passive"))
      (node (ref "C2_BAT3") (pin "2") (pinfunction "2_2") (pintype "passive"))
      (node (ref "C3") (pin "-") (pinfunction "-_-") (pintype "passive"))
      (node (ref "C4_USB") (pin "2") (pinfunction "2_2") (pintype "passive"))
      (node (ref "C5") (pin "2") (pinfunction "2_2") (pintype "passive"))
      (node (ref "C5_USB") (pin "2") (pinfunction "2_2") (pintype "passive"))
      (node (ref "C6") (pin "2") (pinfunction "2_2") (pintype "passive"))
      (node (ref "C7") (pin "2") (pinfunction "2_2") (pintype "passive"))
      (node (ref "C8") (pin "2") (pinfunction "2_2") (pintype "passive"))
      (node (ref "C9") (pin "2") (pinfunction "2_2") (pintype "passive"))
      (node (ref "CHANGE_BUTTON") (pin "1") (pinfunction "1_1") (pintype "passive"))
      (node (ref "CHANGE_BUTTON") (pin "2") (pinfunction "2_2") (pintype "passive"))
      (node (ref "C_DELAY") (pin "2") (pinfunction "2_2") (pintype "passive"))
      (node (ref "D1") (pin "2") (pinfunction "GND_2") (pintype "bidirectional"))
      (node (ref "D10") (pin "1") (pinfunction "1_1") (pintype "passive"))
      (node (ref "D11") (pin "1") (pinfunction "1_1") (pintype "passive"))
      (node (ref "D12") (pin "1") (pinfunction "1_1") (pintype "passive"))
      (node (ref "D3") (pin "1") (pinfunction "K_1") (pintype "bidirectional"))
      (node (ref "D6") (pin "1") (pinfunction "1_1") (pintype "passive"))
      (node (ref "D8") (pin "1") (pinfunction "1_1") (pintype "passive"))
      (node (ref "D9") (pin "1") (pinfunction "1_1") (pintype "passive"))
      (node (ref "EPD_C1") (pin "1") (pinfunction "1_1") (pintype "passive"))
      (node (ref "EPD_C10") (pin "1") (pinfunction "1_1") (pintype "passive"))
      (node (ref "EPD_C11") (pin "1") (pinfunction "1_1") (pintype "passive"))
      (node (ref "EPD_C12") (pin "1") (pinfunction "1_1") (pintype "passive"))
      (node (ref "EPD_C2") (pin "1") (pinfunction "1_1") (pintype "passive"))
      (node (ref "EPD_C5") (pin "1") (pinfunction "1_1") (pintype "passive"))
      (node (ref "EPD_C6") (pin "1") (pinfunction "1_1") (pintype "passive"))
      (node (ref "EPD_C7") (pin "1") (pinfunction "1_1") (pintype "passive"))
      (node (ref "EPD_C8") (pin "1") (pinfunction "1_1") (pintype "passive"))
      (node (ref "EPD_C9") (pin "1") (pinfunction "1_1") (pintype "passive"))
      (node (ref "IC1") (pin "2") (pinfunction "VSS_2") (pintype "bidirectional"))
      (node (ref "IC2") (pin "3") (pinfunction "GND_3") (pintype "bidirectional"))
      (node (ref "J1") (pin "17") (pinfunction "17_17") (pintype "bidirectional"))
      (node (ref "J1") (pin "8") (pinfunction "8_8") (pintype "bidirectional"))
      (node (ref "J1") (pin "MP1") (pinfunction "MP1_MP1") (pintype "bidirectional"))
      (node (ref "J1") (pin "MP2") (pinfunction "MP2_MP2") (pintype "bidirectional"))
      (node (ref "J2") (pin "A1") (pinfunction "A1_A1") (pintype "bidirectional"))
      (node (ref "J2") (pin "A12") (pinfunction "A12_A12") (pintype "bidirectional"))
      (node (ref "J2") (pin "B1") (pinfunction "B1_B1") (pintype "bidirectional"))
      (node (ref "J2") (pin "B12") (pinfunction "B12_B12") (pintype "bidirectional"))
      (node (ref "J2") (pin "MP1") (pinfunction "MP1_MP1") (pintype "bidirectional"))
      (node (ref "J2") (pin "MP2") (pinfunction "MP2_MP2") (pintype "bidirectional"))
      (node (ref "J2") (pin "MP3") (pinfunction "MP3_MP3") (pintype "bidirectional"))
      (node (ref "J2") (pin "MP4") (pinfunction "MP4_MP4") (pintype "bidirectional"))
      (node (ref "J3") (pin "1") (pinfunction "1_1") (pintype "power_in"))
      (node (ref "J4") (pin "G1") (pinfunction "GND_1_G1") (pintype "bidirectional"))
      (node (ref "J4") (pin "G2") (pinfunction "GND_2_G2") (pintype "bidirectional"))
      (node (ref "J4") (pin "G3") (pinfunction "GND_3_G3") (pintype "bidirectional"))
      (node (ref "J4") (pin "G4") (pinfunction "GND_4_G4") (pintype "bidirectional"))
      (node (ref "J4") (pin "P6") (pinfunction "VSS_P6") (pintype "bidirectional"))
      (node (ref "MCP73831") (pin "2") (pinfunction "VSS_2") (pintype "power_in"))
      (node (ref "R1_PWRUSB") (pin "1") (pinfunction "1_1") (pintype "passive"))
      (node (ref "R2") (pin "1") (pinfunction "1_1") (pintype "passive"))
      (node (ref "R2-USB") (pin "2") (pinfunction "2_2") (pintype "passive"))
      (node (ref "R2-USB1") (pin "1") (pinfunction "1_1") (pintype "passive"))
      (node (ref "R2_BAT") (pin "1") (pinfunction "1_1") (pintype "passive"))
      (node (ref "R4") (pin "1") (pinfunction "1_1") (pintype "passive"))
      (node (ref "RESET_BUTTON") (pin "1") (pinfunction "1_1") (pintype "passive"))
      (node (ref "RESET_BUTTON") (pin "2") (pinfunction "2_2") (pintype "passive"))
      (node (ref "SENSOR2") (pin "1") (pinfunction "GND_1") (pintype "power_in"))
      (node (ref "SENSOR2") (pin "5") (pinfunction "SDO_5") (pintype "bidirectional"))
      (node (ref "SENSOR2") (pin "7") (pinfunction "GND_7") (pintype "power_in"))
      (node (ref "SJ1") (pin "1") (pinfunction "1_1") (pintype "passive"))
      (node (ref "TP4") (pin "TP") (pinfunction "TP_TP") (pintype "input"))
      (node (ref "TP5") (pin "TP") (pinfunction "TP_TP") (pintype "input"))
      (node (ref "U1") (pin "4") (pinfunction "GND_4") (pintype "power_in"))
      (node (ref "U1") (pin "9") (pinfunction "EXP_9") (pintype "passive"))
      (node (ref "U2") (pin "1") (pinfunction "GND_1") (pintype "power_in"))
      (node (ref "U2") (pin "28") (pinfunction "GND_28") (pintype "power_in"))
      (node (ref "U2") (pin "29_1") (pinfunction "GND_29_1") (pintype "power_in"))
      (node (ref "U2") (pin "29_2") (pinfunction "GND_29_2") (pintype "power_in"))
      (node (ref "U2") (pin "29_3") (pinfunction "GND_29_3") (pintype "power_in"))
      (node (ref "U2") (pin "29_4") (pinfunction "GND_29_4") (pintype "power_in"))
      (node (ref "U2") (pin "29_5") (pinfunction "GND_29_5") (pintype "power_in"))
      (node (ref "U2") (pin "29_6") (pinfunction "GND_29_6") (pintype "power_in"))
      (node (ref "U2") (pin "29_7") (pinfunction "GND_29_7") (pintype "power_in"))
      (node (ref "U2") (pin "29_8") (pinfunction "GND_29_8") (pintype "power_in"))
      (node (ref "U2") (pin "29_9") (pinfunction "GND_29_9") (pintype "power_in"))
      (node (ref "U3") (pin "13") (pinfunction "GND_13") (pintype "power_in"))
      (node (ref "U4") (pin "1") (pinfunction "CTG_1") (pintype "power_in"))
      (node (ref "U4") (pin "4") (pinfunction "GND_4") (pintype "power_in"))
      (node (ref "U4") (pin "6") (pinfunction "QSTRT_6") (pintype "input"))
      (node (ref "U4") (pin "9") (pinfunction "EP_9") (pintype "power_in"))
    )
    (net (code "16") (name "GPIO8") (class "Default")
      (node (ref "R1") (pin "1") (pinfunction "1_1") (pintype "passive"))
      (node (ref "U2") (pin "10") (pinfunction "IO8_10") (pintype "bidirectional"))
    )
    (net (code "17") (name "I2C_PW") (class "Default")
      (node (ref "SENSOR2") (pin "2") (pinfunction "CSB_2") (pintype "input"))
      (node (ref "SENSOR2") (pin "6") (pinfunction "VDDIO_6") (pintype "power_in"))
      (node (ref "SENSOR2") (pin "8") (pinfunction "VDD_8") (pintype "power_in"))
      (node (ref "U2") (pin "17") (pinfunction "IO19_17") (pintype "bidirectional"))
    )
    (net (code "18") (name "INT_RTC") (class "Default")
      (node (ref "R1_PINH1") (pin "1") (pinfunction "1_1") (pintype "passive"))
      (node (ref "TP15") (pin "TP") (pinfunction "TP_TP") (pintype "input"))
      (node (ref "U2") (pin "8") (pinfunction "IO0_8") (pintype "bidirectional"))
      (node (ref "U3") (pin "3") (pinfunction "SQW/~{INT}_3") (pintype "output"))
    )
    (net (code "19") (name "IO{slash}BOOT") (class "Default")
      (node (ref "BOOT_BUTTON") (pin "3") (pinfunction "3_3") (pintype "passive"))
      (node (ref "BOOT_BUTTON") (pin "4") (pinfunction "4_4") (pintype "passive"))
      (node (ref "C6") (pin "1") (pinfunction "1_1") (pintype "passive"))
      (node (ref "R_BOOT") (pin "1") (pinfunction "1_1") (pintype "passive"))
      (node (ref "U2") (pin "15") (pinfunction "IO9_15") (pintype "bidirectional"))
    )
    (net (code "20") (name "IO{slash}CHANGE") (class "Default")
      (node (ref "C10") (pin "1") (pinfunction "1_1") (pintype "passive"))
      (node (ref "CHANGE_BUTTON") (pin "3") (pinfunction "3_3") (pintype "passive"))
      (node (ref "CHANGE_BUTTON") (pin "4") (pinfunction "4_4") (pintype "passive"))
      (node (ref "R_CHANGE") (pin "1") (pinfunction "1_1") (pintype "passive"))
      (node (ref "U2") (pin "23") (pinfunction "IO15_23") (pintype "bidirectional"))
    )
    (net (code "21") (name "MISO") (class "Default")
      (node (ref "D12") (pin "2") (pinfunction "2_2") (pintype "passive"))
      (node (ref "J4") (pin "P7") (pinfunction "DAT0_P7") (pintype "bidirectional"))
      (node (ref "R8") (pin "1") (pinfunction "1_1") (pintype "passive"))
      (node (ref "TP6") (pin "TP") (pinfunction "TP_TP") (pintype "input"))
      (node (ref "U1") (pin "2") (pinfunction "DO(IO1)_2") (pintype "bidirectional"))
      (node (ref "U2") (pin "27") (pinfunction "IO2_27") (pintype "bidirectional"))
    )
    (net (code "22") (name "MOSI") (class "Default")
      (node (ref "D11") (pin "2") (pinfunction "2_2") (pintype "passive"))
      (node (ref "J1") (pin "14") (pinfunction "14_14") (pintype "bidirectional"))
      (node (ref "J4") (pin "P3") (pinfunction "CMD_P3") (pintype "bidirectional"))
      (node (ref "R7") (pin "1") (pinfunction "1_1") (pintype "passive"))
      (node (ref "TP7") (pin "TP") (pinfunction "TP_TP") (pintype "input"))
      (node (ref "U1") (pin "5") (pinfunction "DI(IO0)_5") (pintype "bidirectional"))
      (node (ref "U2") (pin "7") (pinfunction "IO7_7") (pintype "bidirectional"))
    )
    (net (code "23") (name "Net-(D2-CATHODE)") (class "Default")
      (node (ref "C1_BAT1") (pin "1") (pinfunction "1_1") (pintype "passive"))
      (node (ref "D2") (pin "1") (pinfunction "CATHODE_1") (pintype "bidirectional"))
      (node (ref "IC1") (pin "1") (pinfunction "VIN_1") (pintype "bidirectional"))
      (node (ref "IC1") (pin "3") (pinfunction "CE_3") (pintype "bidirectional"))
      (node (ref "Q1") (pin "2") (pinfunction "S_2") (pintype "bidirectional"))
    )
    (net (code "24") (name "Net-(D3-A)") (class "Default")
      (node (ref "C4") (pin "1") (pinfunction "1_1") (pintype "passive"))
      (node (ref "D3") (pin "2") (pinfunction "A_2") (pintype "bidirectional"))
      (node (ref "D4") (pin "1") (pinfunction "K_1") (pintype "bidirectional"))
    )
    (net (code "25") (name "Net-(D7-CATHODE)") (class "Default")
      (node (ref "D7") (pin "1") (pinfunction "CATHODE_1") (pintype "bidirectional"))
      (node (ref "R_CAPACITOR") (pin "1") (pinfunction "1_1") (pintype "passive"))
    )
    (net (code "26") (name "Net-(EPD_C1-Pad2)") (class "Default")
      (node (ref "EPD_C1") (pin "2") (pinfunction "2_2") (pintype "passive"))
      (node (ref "J1") (pin "4") (pinfunction "4_4") (pintype "bidirectional"))
    )
    (net (code "27") (name "Net-(EPD_C2-Pad2)") (class "Default")
      (node (ref "EPD_C2") (pin "2") (pinfunction "2_2") (pintype "passive"))
      (node (ref "J1") (pin "5") (pinfunction "5_5") (pintype "bidirectional"))
    )
    (net (code "28") (name "Net-(EPD_C6-Pad2)") (class "Default")
      (node (ref "EPD_C6") (pin "2") (pinfunction "2_2") (pintype "passive"))
      (node (ref "J1") (pin "18") (pinfunction "18_18") (pintype "bidirectional"))
    )
    (net (code "29") (name "Net-(EPD_C7-Pad2)") (class "Default")
      (node (ref "EPD_C7") (pin "2") (pinfunction "2_2") (pintype "passive"))
      (node (ref "J1") (pin "19") (pinfunction "19_19") (pintype "bidirectional"))
    )
    (net (code "30") (name "Net-(EPD_C8-Pad2)") (class "Default")
      (node (ref "EPD_C8") (pin "2") (pinfunction "2_2") (pintype "passive"))
      (node (ref "J1") (pin "20") (pinfunction "20_20") (pintype "bidirectional"))
    )
    (net (code "31") (name "Net-(EPD_C10-Pad2)") (class "Default")
      (node (ref "EPD_C10") (pin "2") (pinfunction "2_2") (pintype "passive"))
      (node (ref "J1") (pin "22") (pinfunction "22_22") (pintype "bidirectional"))
    )
    (net (code "32") (name "Net-(EPD_C12-Pad2)") (class "Default")
      (node (ref "EPD_C12") (pin "2") (pinfunction "2_2") (pintype "passive"))
      (node (ref "J1") (pin "24") (pinfunction "24_24") (pintype "bidirectional"))
    )
    (net (code "33") (name "Net-(IC2-CT)") (class "Default")
      (node (ref "C_DELAY") (pin "1") (pinfunction "1_1") (pintype "passive"))
      (node (ref "IC2") (pin "5") (pinfunction "CT_5") (pintype "bidirectional"))
    )
    (net (code "34") (name "Net-(J2-PadA5)") (class "Default")
      (node (ref "J2") (pin "A5") (pinfunction "A5_A5") (pintype "bidirectional"))
      (node (ref "R2-USB1") (pin "2") (pinfunction "2_2") (pintype "passive"))
    )
    (net (code "35") (name "Net-(J2-PadB5)") (class "Default")
      (node (ref "J2") (pin "B5") (pinfunction "B5_B5") (pintype "bidirectional"))
      (node (ref "R2-USB") (pin "1") (pinfunction "1_1") (pintype "passive"))
    )
    (net (code "36") (name "Net-(LED1-PadC)") (class "Default")
      (node (ref "LED1") (pin "C") (pinfunction "C_C") (pintype "passive"))
      (node (ref "R1_BAT") (pin "1") (pinfunction "1_1") (pintype "passive"))
    )
    (net (code "37") (name "Net-(MCP73831-PROG)") (class "Default")
      (node (ref "MCP73831") (pin "5") (pinfunction "PROG_5") (pintype "input"))
      (node (ref "R2_BAT") (pin "2") (pinfunction "2_2") (pintype "passive"))
    )
    (net (code "38") (name "Net-(MCP73831-STAT)") (class "Default")
      (node (ref "MCP73831") (pin "1") (pinfunction "STAT_1") (pintype "output"))
      (node (ref "R1_BAT") (pin "2") (pinfunction "2_2") (pintype "passive"))
    )
    (net (code "39") (name "PREVGH") (class "Default")
      (node (ref "D5") (pin "1") (pinfunction "K_1") (pintype "bidirectional"))
      (node (ref "EPD_C9") (pin "2") (pinfunction "2_2") (pintype "passive"))
      (node (ref "J1") (pin "21") (pinfunction "21_21") (pintype "bidirectional"))
    )
    (net (code "40") (name "PREVGL") (class "Default")
      (node (ref "D4") (pin "2") (pinfunction "A_2") (pintype "bidirectional"))
      (node (ref "EPD_C11") (pin "2") (pinfunction "2_2") (pintype "passive"))
      (node (ref "J1") (pin "23") (pinfunction "23_23") (pintype "bidirectional"))
    )
    (net (code "41") (name "RESE") (class "Default")
      (node (ref "J1") (pin "3") (pinfunction "3_3") (pintype "bidirectional"))
      (node (ref "Q3") (pin "2") (pinfunction "S_2") (pintype "bidirectional"))
      (node (ref "R3") (pin "2") (pinfunction "2_2") (pintype "passive"))
    )
    (net (code "42") (name "RESE'") (class "Default")
      (node (ref "R2") (pin "2") (pinfunction "2_2") (pintype "passive"))
      (node (ref "R3") (pin "1") (pinfunction "1_1") (pintype "passive"))
      (node (ref "SJ1") (pin "2") (pinfunction "2_2") (pintype "passive"))
    )
    (net (code "43") (name "RESET") (class "Default")
      (node (ref "C5") (pin "1") (pinfunction "1_1") (pintype "passive"))
      (node (ref "IC2") (pin "1") (pinfunction "VOUT_1") (pintype "bidirectional"))
      (node (ref "RESET_BUTTON") (pin "3") (pinfunction "3_3") (pintype "passive"))
      (node (ref "RESET_BUTTON") (pin "4") (pinfunction "4_4") (pintype "passive"))
      (node (ref "R_RESET") (pin "1") (pinfunction "1_1") (pintype "passive"))
      (node (ref "U2") (pin "3") (pinfunction "EN_3") (pintype "input"))
    )
    (net (code "44") (name "RTC_RST") (class "Default")
      (node (ref "U2") (pin "16") (pinfunction "IO18_16") (pintype "bidirectional"))
      (node (ref "U3") (pin "4") (pinfunction "~{RST}_4") (pintype "input"))
    )
    (net (code "45") (name "RX") (class "Default")
      (node (ref "TP2") (pin "TP") (pinfunction "TP_TP") (pintype "input"))
      (node (ref "U2") (pin "24") (pinfunction "RXD0/GPIO17_24") (pintype "bidirectional"))
    )
    (net (code "46") (name "SCK") (class "Default")
      (node (ref "D10") (pin "2") (pinfunction "2_2") (pintype "passive"))
      (node (ref "J1") (pin "13") (pinfunction "13_13") (pintype "bidirectional"))
      (node (ref "J4") (pin "P5") (pinfunction "CLK_P5") (pintype "bidirectional"))
      (node (ref "R6") (pin "1") (pinfunction "1_1") (pintype "passive"))
      (node (ref "TP8") (pin "TP") (pinfunction "TP_TP") (pintype "input"))
      (node (ref "U1") (pin "6") (pinfunction "CLK_6") (pintype "input"))
      (node (ref "U2") (pin "6") (pinfunction "IO6_6") (pintype "bidirectional"))
    )
    (net (code "47") (name "SCL") (class "Default")
      (node (ref "J3") (pin "4") (pinfunction "4_4") (pintype "passive"))
      (node (ref "R2-PINH") (pin "1") (pinfunction "1_1") (pintype "passive"))
      (node (ref "SENSOR2") (pin "4") (pinfunction "SCK_4") (pintype "input"))
      (node (ref "U2") (pin "20") (pinfunction "IO22_20") (pintype "bidirectional"))
      (node (ref "U3") (pin "16") (pinfunction "SCL_16") (pintype "input"))
      (node (ref "U4") (pin "7") (pinfunction "SCL_7") (pintype "input"))
    )
    (net (code "48") (name "SDA") (class "Default")
      (node (ref "J3") (pin "3") (pinfunction "3_3") (pintype "passive"))
      (node (ref "R1_PINH") (pin "1") (pinfunction "1_1") (pintype "passive"))
      (node (ref "SENSOR2") (pin "3") (pinfunction "SDI_3") (pintype "bidirectional"))
      (node (ref "U2") (pin "19") (pinfunction "IO21_19") (pintype "bidirectional"))
      (node (ref "U3") (pin "15") (pinfunction "SDA_15") (pintype "bidirectional"))
      (node (ref "U4") (pin "8") (pinfunction "SDA_8") (pintype "bidirectional"))
    )
    (net (code "49") (name "SRC") (class "Default")
      (node (ref "C4") (pin "2") (pinfunction "2_2") (pintype "passive"))
      (node (ref "D5") (pin "2") (pinfunction "A_2") (pintype "bidirectional"))
      (node (ref "L1") (pin "1") (pinfunction "1_1") (pintype "passive"))
      (node (ref "Q3") (pin "3") (pinfunction "D_3") (pintype "bidirectional"))
    )
    (net (code "50") (name "SS_SD") (class "Default")
      (node (ref "D8") (pin "2") (pinfunction "2_2") (pintype "passive"))
      (node (ref "J4") (pin "P2") (pinfunction "CD/DAT3_P2") (pintype "bidirectional"))
      (node (ref "R10") (pin "1") (pinfunction "1_1") (pintype "passive"))
      (node (ref "U2") (pin "4") (pinfunction "IO4_4") (pintype "bidirectional"))
    )
    (net (code "51") (name "TX") (class "Default")
      (node (ref "TP1") (pin "TP") (pinfunction "TP_TP") (pintype "input"))
      (node (ref "U2") (pin "25") (pinfunction "TXD0/GPIO16_25") (pintype "bidirectional"))
    )
    (net (code "52") (name "USB_D+") (class "Default")
      (node (ref "D1") (pin "1") (pinfunction "I/O1_1_1") (pintype "bidirectional"))
      (node (ref "U2") (pin "14") (pinfunction "IO13_14") (pintype "bidirectional"))
    )
    (net (code "53") (name "USB_D-") (class "Default")
      (node (ref "D1") (pin "3") (pinfunction "I/O2_1_3") (pintype "bidirectional"))
      (node (ref "U2") (pin "13") (pinfunction "IO12_13") (pintype "bidirectional"))
    )
    (net (code "54") (name "VBAT") (class "Default")
      (node (ref "C2_BAT3") (pin "1") (pinfunction "1_1") (pintype "passive"))
      (node (ref "MCP73831") (pin "3") (pinfunction "VBAT_3") (pintype "power_in"))
      (node (ref "Q1") (pin "3") (pinfunction "D_3") (pintype "bidirectional"))
      (node (ref "TP3") (pin "TP") (pinfunction "TP_TP") (pintype "input"))
      (node (ref "U4") (pin "2") (pinfunction "CELL_2") (pintype "power_in"))
      (node (ref "U4") (pin "3") (pinfunction "VDD_3") (pintype "power_in"))
    )
    (net (code "55") (name "VBUS") (class "Default")
      (node (ref "C1_BAT") (pin "1") (pinfunction "1_1") (pintype "passive"))
      (node (ref "C4_USB") (pin "1") (pinfunction "1_1") (pintype "passive"))
      (node (ref "C5_USB") (pin "1") (pinfunction "1_1") (pintype "passive"))
      (node (ref "D1") (pin "5") (pinfunction "VBUS_5") (pintype "bidirectional"))
      (node (ref "D2") (pin "2") (pinfunction "ANODE_2") (pintype "bidirectional"))
      (node (ref "LED1") (pin "A") (pinfunction "A_A") (pintype "passive"))
      (node (ref "MCP73831") (pin "4") (pinfunction "VIN_4") (pintype "power_in"))
      (node (ref "PFMF.050.1") (pin "2") (pinfunction "2_2") (pintype "passive"))
      (node (ref "Q1") (pin "1") (pinfunction "G_1") (pintype "bidirectional"))
      (node (ref "R1_PWRUSB") (pin "2") (pinfunction "2_2") (pintype "passive"))
      (node (ref "TP14") (pin "TP") (pinfunction "TP_TP") (pintype "input"))
    )
    (net (code "56") (name "VRTC") (class "Default")
      (node (ref "C10_SUPERCAP") (pin "1") (pinfunction "1_1") (pintype "passive"))
      (node (ref "C8") (pin "1") (pinfunction "1_1") (pintype "passive"))
      (node (ref "R_CAPACITOR") (pin "2") (pinfunction "2_2") (pintype "passive"))
      (node (ref "U3") (pin "14") (pinfunction "VBAT_14") (pintype "power_in"))
    )
    (net (code "57") (name "VUSB") (class "Default")
      (node (ref "J2") (pin "A4") (pinfunction "A4_A4") (pintype "bidirectional"))
      (node (ref "J2") (pin "A9") (pinfunction "A9_A9") (pintype "bidirectional"))
      (node (ref "J2") (pin "B4") (pinfunction "B4_B4") (pintype "bidirectional"))
      (node (ref "J2") (pin "B9") (pinfunction "B9_B9") (pintype "bidirectional"))
      (node (ref "PFMF.050.1") (pin "1") (pinfunction "1_1") (pintype "passive"))
    )
    (net (code "58") (name "unconnected-(IC1-NC-Pad4)") (class "Default")
      (node (ref "IC1") (pin "4") (pinfunction "NC_4") (pintype "no_connect"))
    )
    (net (code "59") (name "unconnected-(IC2-NC-Pad4)") (class "Default")
      (node (ref "IC2") (pin "4") (pinfunction "NC_4") (pintype "no_connect"))
    )
    (net (code "60") (name "unconnected-(J1-Pad1)") (class "Default")
      (node (ref "J1") (pin "1") (pinfunction "1_1") (pintype "bidirectional"))
    )
    (net (code "61") (name "unconnected-(J1-Pad6)") (class "Default")
      (node (ref "J1") (pin "6") (pinfunction "6_6") (pintype "bidirectional"))
    )
    (net (code "62") (name "unconnected-(J1-Pad7)") (class "Default")
      (node (ref "J1") (pin "7") (pinfunction "7_7") (pintype "bidirectional"))
    )
    (net (code "63") (name "unconnected-(J2-PadA8)") (class "Default")
      (node (ref "J2") (pin "A8") (pinfunction "A8_A8") (pintype "bidirectional"))
    )
    (net (code "64") (name "unconnected-(J2-PadB8)") (class "Default")
      (node (ref "J2") (pin "B8") (pinfunction "B8_B8") (pintype "bidirectional"))
    )
    (net (code "65") (name "unconnected-(J4-DAT1-PadP8)") (class "Default")
      (node (ref "J4") (pin "P8") (pinfunction "DAT1_P8") (pintype "bidirectional"))
    )
    (net (code "66") (name "unconnected-(J4-DAT2-PadP1)") (class "Default")
      (node (ref "J4") (pin "P1") (pinfunction "DAT2_P1") (pintype "bidirectional"))
    )
    (net (code "67") (name "unconnected-(J4-DETECTION_1-PadS1)") (class "Default")
      (node (ref "J4") (pin "S1") (pinfunction "DETECTION_1_S1") (pintype "bidirectional"))
    )
    (net (code "68") (name "unconnected-(J4-DETECTION_2-PadS2)") (class "Default")
      (node (ref "J4") (pin "S2") (pinfunction "DETECTION_2_S2") (pintype "bidirectional"))
    )
    (net (code "69") (name "unconnected-(U2-NC-Pad22)") (class "Default")
      (node (ref "U2") (pin "22") (pinfunction "NC_22") (pintype "no_connect"))
    )
    (net (code "70") (name "unconnected-(U4-~{ALERT}-Pad5)") (class "Default")
      (node (ref "U4") (pin "5") (pinfunction "~{ALERT}_5") (pintype "output"))
    )
  )
)
